# System.net
KiCad netlist of a schematic drawn in Altium Designer
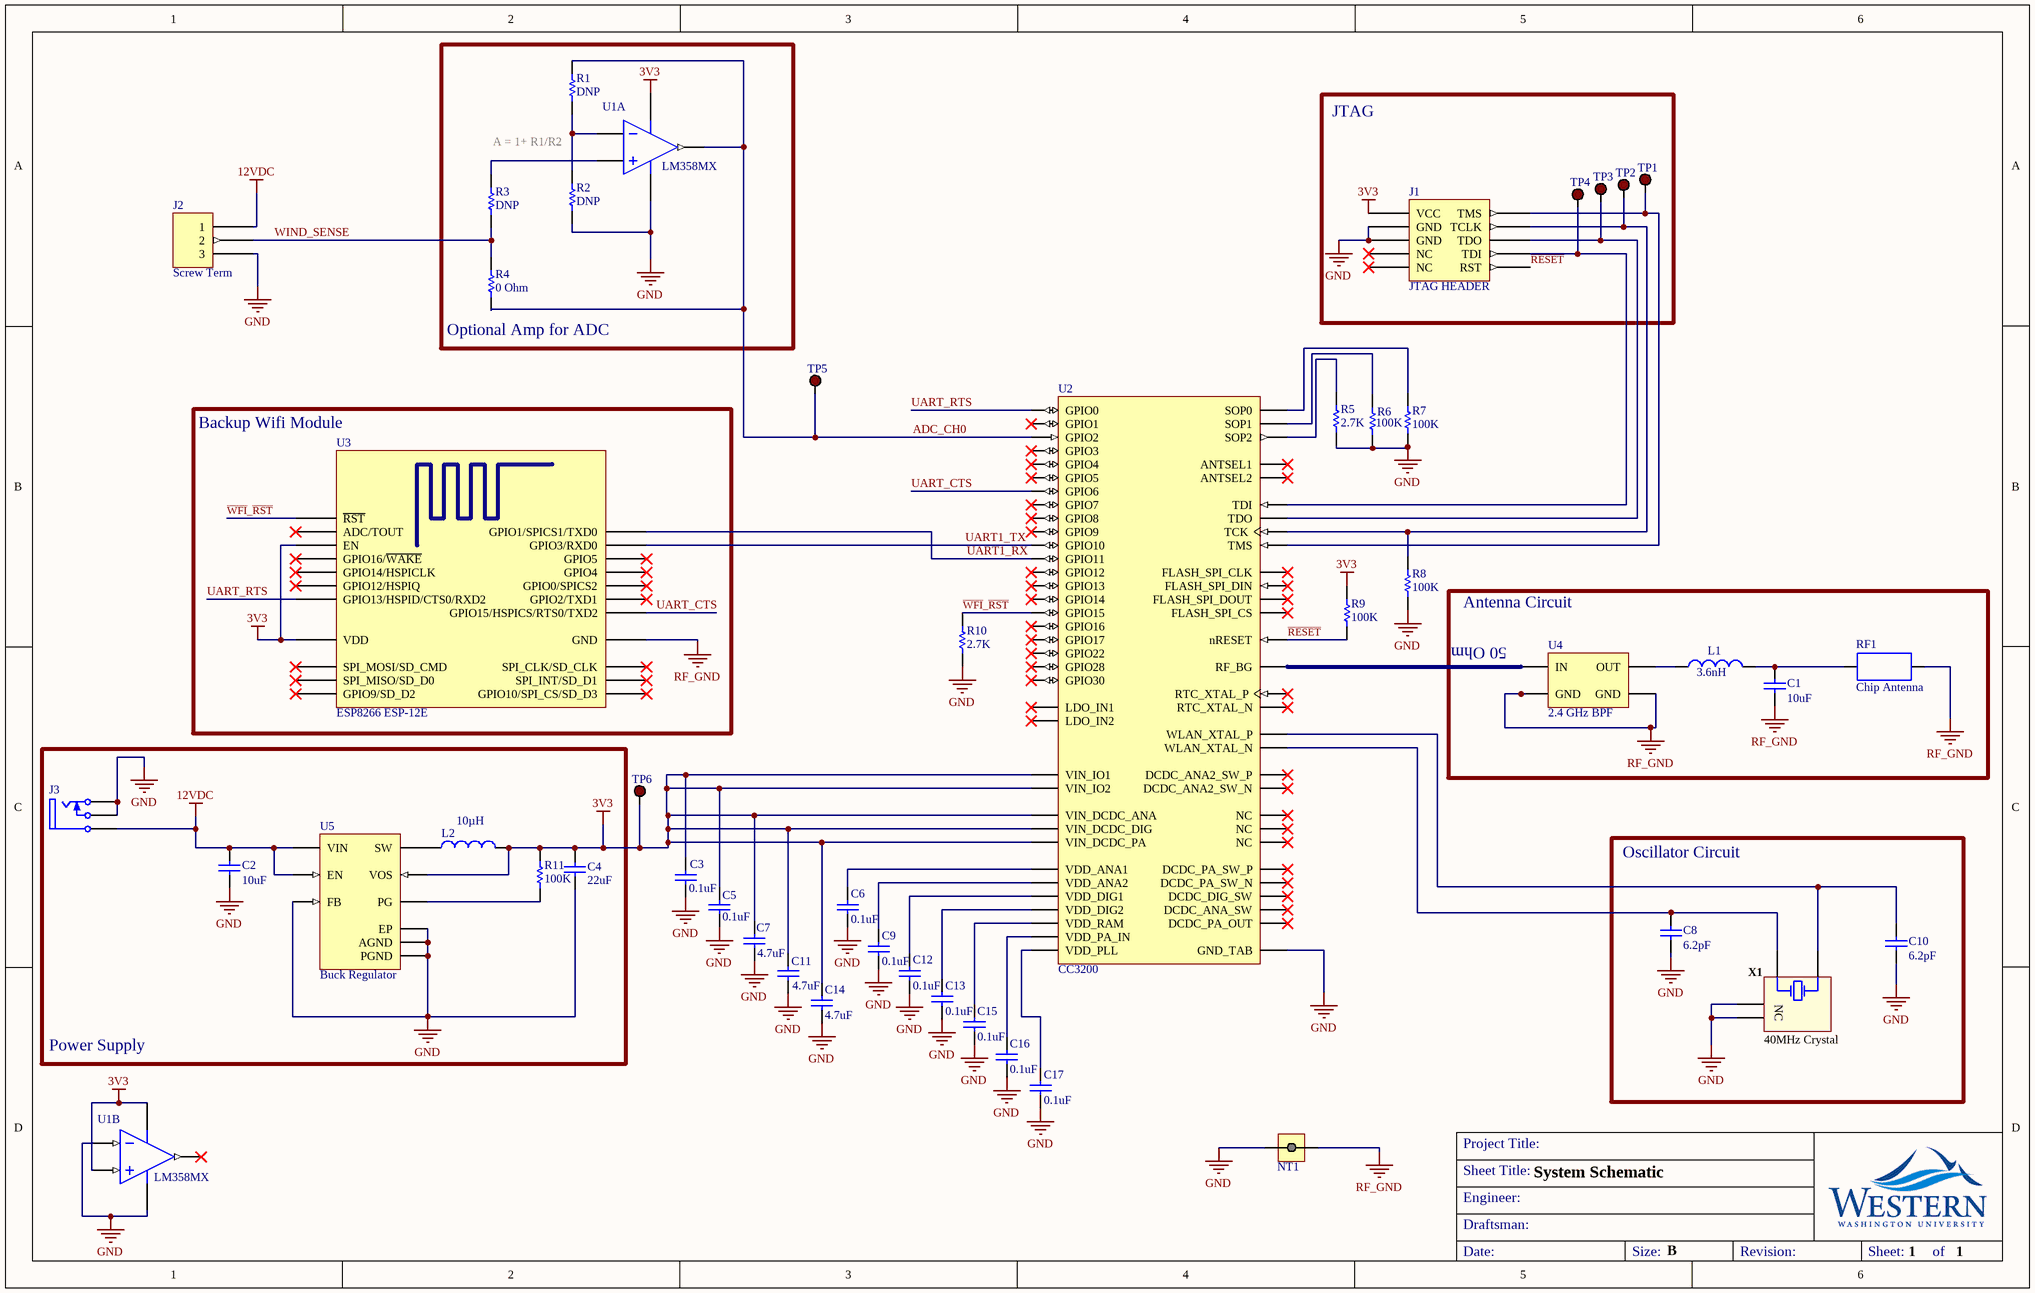
[diagram p0: System.SchDoc]

(export (version "E")
  (design (tool "Eeschema 10.0.6"))
  (components
    (comp (ref "C1")
      (value "10uF")
      (footprint "CAPC0603(1608)100_M")
      (description "CAP 10uF 10V ±20% 0603 (1608 Metric) Thickness 1mm SMD")
      (fields (field (name "TOLERANCE") "Â±20%") (field (name "Comment") "CAP 10uF 10V 0603(1608)"))
      (libsource (lib "Altium Content Vault") (part "CMP-1035-02800-1"))
    )
    (comp (ref "C2")
      (value "10uF")
      (footprint "CAPC0603(1608)100_M")
      (description "CAP 10uF 10V ±20% 0603 (1608 Metric) Thickness 1mm SMD")
      (fields (field (name "TOLERANCE") "Â±20%") (field (name "Comment") "CAP 10uF 10V 0603(1608)"))
      (libsource (lib "Altium Content Vault") (part "CMP-1035-02800-1"))
    )
    (comp (ref "C3")
      (value "0.1uF")
      (footprint "CAPC0603(1608)100_M")
      (description "CAP 10uF 10V ±20% 0603 (1608 Metric) Thickness 1mm SMD")
      (fields (field (name "TOLERANCE") "Â±20%") (field (name "Comment") "CAP 10uF 10V 0603(1608)"))
      (libsource (lib "Altium Content Vault") (part "CMP-1035-02800-1"))
    )
    (comp (ref "C4")
      (value "22uF")
      (footprint "CAPC0603(1608)100_L")
      (description "0603 (1608 Metric) Chip Capacitor")
      (libsource (lib "Altium Content Vault") (part "CAP_5"))
    )
    (comp (ref "C5")
      (value "0.1uF")
      (footprint "CAPC0603(1608)100_M")
      (description "CAP 10uF 10V ±20% 0603 (1608 Metric) Thickness 1mm SMD")
      (fields (field (name "TOLERANCE") "Â±20%") (field (name "Comment") "CAP 10uF 10V 0603(1608)"))
      (libsource (lib "Altium Content Vault") (part "CMP-1035-02800-1"))
    )
    (comp (ref "C6")
      (value "0.1uF")
      (footprint "CAPC0603(1608)100_M")
      (description "CAP 10uF 10V ±20% 0603 (1608 Metric) Thickness 1mm SMD")
      (fields (field (name "TOLERANCE") "Â±20%") (field (name "Comment") "CAP 10uF 10V 0603(1608)"))
      (libsource (lib "Altium Content Vault") (part "CMP-1035-02800-1"))
    )
    (comp (ref "C7")
      (value "4.7uF")
      (footprint "CAPC0603(1608)100_M")
      (description "CAP 10uF 10V ±20% 0603 (1608 Metric) Thickness 1mm SMD")
      (fields (field (name "TOLERANCE") "Â±20%") (field (name "Comment") "CAP 10uF 10V 0603(1608)"))
      (libsource (lib "Altium Content Vault") (part "CMP-1035-02800-1"))
    )
    (comp (ref "C8")
      (value "6.2pF")
      (footprint "CAPC0603(1608)100_M")
      (description "CAP 10uF 10V ±20% 0603 (1608 Metric) Thickness 1mm SMD")
      (fields (field (name "TOLERANCE") "Â±20%") (field (name "Comment") "CAP 10uF 10V 0603(1608)"))
      (libsource (lib "Altium Content Vault") (part "CMP-1035-02800-1"))
    )
    (comp (ref "C9")
      (value "0.1uF")
      (footprint "CAPC0603(1608)100_M")
      (description "CAP 10uF 10V ±20% 0603 (1608 Metric) Thickness 1mm SMD")
      (fields (field (name "TOLERANCE") "Â±20%") (field (name "Comment") "CAP 10uF 10V 0603(1608)"))
      (libsource (lib "Altium Content Vault") (part "CMP-1035-02800-1"))
    )
    (comp (ref "C10")
      (value "6.2pF")
      (footprint "CAPC0603(1608)100_M")
      (description "CAP 10uF 10V ±20% 0603 (1608 Metric) Thickness 1mm SMD")
      (fields (field (name "TOLERANCE") "Â±20%") (field (name "Comment") "CAP 10uF 10V 0603(1608)"))
      (libsource (lib "Altium Content Vault") (part "CMP-1035-02800-1"))
    )
    (comp (ref "C11")
      (value "4.7uF")
      (footprint "CAPC0603(1608)100_M")
      (description "CAP 10uF 10V ±20% 0603 (1608 Metric) Thickness 1mm SMD")
      (fields (field (name "TOLERANCE") "Â±20%") (field (name "Comment") "CAP 10uF 10V 0603(1608)"))
      (libsource (lib "Altium Content Vault") (part "CMP-1035-02800-1"))
    )
    (comp (ref "C12")
      (value "0.1uF")
      (footprint "CAPC0603(1608)100_M")
      (description "CAP 10uF 10V ±20% 0603 (1608 Metric) Thickness 1mm SMD")
      (fields (field (name "TOLERANCE") "Â±20%") (field (name "Comment") "CAP 10uF 10V 0603(1608)"))
      (libsource (lib "Altium Content Vault") (part "CMP-1035-02800-1"))
    )
    (comp (ref "C13")
      (value "0.1uF")
      (footprint "CAPC0603(1608)100_M")
      (description "CAP 10uF 10V ±20% 0603 (1608 Metric) Thickness 1mm SMD")
      (fields (field (name "TOLERANCE") "Â±20%") (field (name "Comment") "CAP 10uF 10V 0603(1608)"))
      (libsource (lib "Altium Content Vault") (part "CMP-1035-02800-1"))
    )
    (comp (ref "C14")
      (value "4.7uF")
      (footprint "CAPC0603(1608)100_M")
      (description "CAP 10uF 10V ±20% 0603 (1608 Metric) Thickness 1mm SMD")
      (fields (field (name "TOLERANCE") "Â±20%") (field (name "Comment") "CAP 10uF 10V 0603(1608)"))
      (libsource (lib "Altium Content Vault") (part "CMP-1035-02800-1"))
    )
    (comp (ref "C15")
      (value "0.1uF")
      (footprint "CAPC0603(1608)100_M")
      (description "CAP 10uF 10V ±20% 0603 (1608 Metric) Thickness 1mm SMD")
      (fields (field (name "TOLERANCE") "Â±20%") (field (name "Comment") "CAP 10uF 10V 0603(1608)"))
      (libsource (lib "Altium Content Vault") (part "CMP-1035-02800-1"))
    )
    (comp (ref "C16")
      (value "0.1uF")
      (footprint "CAPC0603(1608)100_M")
      (description "CAP 10uF 10V ±20% 0603 (1608 Metric) Thickness 1mm SMD")
      (fields (field (name "TOLERANCE") "Â±20%") (field (name "Comment") "CAP 10uF 10V 0603(1608)"))
      (libsource (lib "Altium Content Vault") (part "CMP-1035-02800-1"))
    )
    (comp (ref "C17")
      (value "0.1uF")
      (footprint "CAPC0603(1608)100_M")
      (description "CAP 10uF 10V ±20% 0603 (1608 Metric) Thickness 1mm SMD")
      (fields (field (name "TOLERANCE") "Â±20%") (field (name "Comment") "CAP 10uF 10V 0603(1608)"))
      (libsource (lib "Altium Content Vault") (part "CMP-1035-02800-1"))
    )
    (comp (ref "J1")
      (value "JTAG HEADER")
      (footprint "FTSH-105-01-L-DV-K")
      (description "10 pin 0.05\" pitch header for JTAG")
      (libsource (lib "WWUEE_SchematicLibrary") (part "JTAG 10 PIN HEADER"))
    )
    (comp (ref "J2")
      (value "Screw Term")
      (footprint "SCREW TERM 3 PIN 3.5mm")
      (libsource (lib "WWUEE_SchematicLibrary") (part "SCREW TERM 3.5mm 3pos"))
    )
    (comp (ref "J3")
      (value "RASM722X")
      (footprint "SWIT-RASM722X_V")
      (description "Power Jack, 5 A, 250 V, 3-Pin SMD, RoHS, Bulk")
      (libsource (lib "Altium Content Vault") (part "CMP-1772-00002-1"))
    )
    (comp (ref "L1")
      (value "MLZ2012N100LT")
      (footprint "TDK-IND0805-125_V")
      (description "Multilayer Inductor, 10 uH, ±20%, 300 mOhm, 50MHz, 0805(2012)")
      (fields
        (field (name "MANUFACTURER") "TDK Corporation")
        (field (name "MANUFACTURER PART NUMBER") "MLZ2012N100LTD25")
        (field (name "INDUCTANCE") "3.6nH")
      )
      (libsource (lib "Altium Content Vault") (part "CMP-0266-00001-1"))
    )
    (comp (ref "L2")
      (value "MLZ2012N100LT")
      (footprint "TDK-IND0805-125_V")
      (description "Multilayer Inductor, 10 uH, ±20%, 300 mOhm, 50MHz, 0805(2012)")
      (fields
        (field (name "MANUFACTURER") "TDK Corporation")
        (field (name "MANUFACTURER PART NUMBER") "MLZ2012N100LTD25")
        (field (name "INDUCTANCE") "10µH")
      )
      (libsource (lib "Altium Content Vault") (part "CMP-0266-00001-1"))
    )
    (comp (ref "NT1")
      (value "NET TIE 0603")
      (footprint "NetTie0603")
      (libsource (lib "WWUEE_SchematicLibrary") (part "NET TIE"))
    )
    (comp (ref "R1")
      (value "DNP")
      (footprint "RESC0603(1608)_N")
      (description "Jumper 0603 (1608 Metric)")
      (fields (field (name "POWER") "None"))
      (libsource (lib "Altium Content Vault") (part "CMP-1012-00001-1"))
    )
    (comp (ref "R2")
      (value "DNP")
      (footprint "RESC0603(1608)_N")
      (description "Jumper 0603 (1608 Metric)")
      (fields (field (name "POWER") "None"))
      (libsource (lib "Altium Content Vault") (part "CMP-1012-00001-1"))
    )
    (comp (ref "R3")
      (value "DNP")
      (footprint "RESC0603(1608)_N")
      (description "Jumper 0603 (1608 Metric)")
      (fields (field (name "POWER") "None"))
      (libsource (lib "Altium Content Vault") (part "CMP-1012-00001-1"))
    )
    (comp (ref "R4")
      (value "0 Ohm")
      (footprint "RESC0603(1608)_N")
      (description "Jumper 0603 (1608 Metric)")
      (fields (field (name "POWER") "None"))
      (libsource (lib "Altium Content Vault") (part "RES"))
    )
    (comp (ref "R5")
      (value "2.7K")
      (footprint "RESC0805(2012)_L")
      (description "100K 0.125W 5% 0805 (2012 Metric)  SMD")
      (fields (field (name "TOLERANCE") "5 %") (field (name "POWER") "0.125 W"))
      (libsource (lib "Altium Content Vault") (part "RES"))
    )
    (comp (ref "R6")
      (value "100K")
      (footprint "RESC0805(2012)_L")
      (description "100K 0.125W 5% 0805 (2012 Metric)  SMD")
      (fields (field (name "TOLERANCE") "5 %") (field (name "POWER") "0.125 W"))
      (libsource (lib "Altium Content Vault") (part "RES"))
    )
    (comp (ref "R7")
      (value "100K")
      (footprint "RESC0805(2012)_L")
      (description "100K 0.125W 5% 0805 (2012 Metric)  SMD")
      (fields (field (name "TOLERANCE") "5 %") (field (name "POWER") "0.125 W"))
      (libsource (lib "Altium Content Vault") (part "RES"))
    )
    (comp (ref "R8")
      (value "100K")
      (footprint "RESC0805(2012)_L")
      (description "100K 0.125W 5% 0805 (2012 Metric)  SMD")
      (fields (field (name "TOLERANCE") "5 %") (field (name "POWER") "0.125 W"))
      (libsource (lib "Altium Content Vault") (part "RES"))
    )
    (comp (ref "R9")
      (value "100K")
      (footprint "RESC0805(2012)_L")
      (description "100K 0.125W 5% 0805 (2012 Metric)  SMD")
      (fields (field (name "TOLERANCE") "5 %") (field (name "POWER") "0.125 W"))
      (libsource (lib "Altium Content Vault") (part "RES"))
    )
    (comp (ref "R10")
      (value "2.7K")
      (footprint "RESC0805(2012)_L")
      (description "100K 0.125W 5% 0805 (2012 Metric)  SMD")
      (fields (field (name "TOLERANCE") "5 %") (field (name "POWER") "0.125 W"))
      (libsource (lib "Altium Content Vault") (part "RES"))
    )
    (comp (ref "R11")
      (value "100K")
      (footprint "RESC0805(2012)_L")
      (description "100K 0.125W 5% 0805 (2012 Metric)  SMD")
      (fields (field (name "TOLERANCE") "5 %") (field (name "POWER") "0.125 W"))
      (libsource (lib "Altium Content Vault") (part "RES"))
    )
    (comp (ref "RF1")
      (value "Chip Antenna")
      (footprint "TAYO-AH316M-2_N")
      (description "Chip Antenna, 2.4 to 2.5 GHz, -40 to 85 degC, 2-Pin SMD, Pb-Free, Tape and Reel")
      (fields (field (name "TOLERANCE") "10%"))
      (libsource (lib "Altium Content Vault") (part "CMP-1660-00004-1"))
    )
    (comp (ref "TP1")
      (value "5001")
      (footprint "Keystone_5001")
      (description "TEST POINT PC MINI .040\"D BLACK")
      (fields (field (name "MANUFACTURER") "Keystone Electronics"))
      (libsource (lib "WWUEE_SchematicLibrary") (part "TEST POINT"))
    )
    (comp (ref "TP2")
      (value "5001")
      (footprint "Keystone_5001")
      (description "TEST POINT PC MINI .040\"D BLACK")
      (fields (field (name "MANUFACTURER") "Keystone Electronics"))
      (libsource (lib "WWUEE_SchematicLibrary") (part "TEST POINT"))
    )
    (comp (ref "TP3")
      (value "5001")
      (footprint "Keystone_5001")
      (description "TEST POINT PC MINI .040\"D BLACK")
      (fields (field (name "MANUFACTURER") "Keystone Electronics"))
      (libsource (lib "WWUEE_SchematicLibrary") (part "TEST POINT"))
    )
    (comp (ref "TP4")
      (value "5001")
      (footprint "Keystone_5001")
      (description "TEST POINT PC MINI .040\"D BLACK")
      (fields (field (name "MANUFACTURER") "Keystone Electronics"))
      (libsource (lib "WWUEE_SchematicLibrary") (part "TEST POINT"))
    )
    (comp (ref "TP5")
      (value "5001")
      (footprint "Keystone_5001")
      (description "TEST POINT PC MINI .040\"D BLACK")
      (fields (field (name "MANUFACTURER") "Keystone Electronics"))
      (libsource (lib "WWUEE_SchematicLibrary") (part "TEST POINT"))
    )
    (comp (ref "TP6")
      (value "5001")
      (footprint "Keystone_5001")
      (description "TEST POINT PC MINI .040\"D BLACK")
      (fields (field (name "MANUFACTURER") "Keystone Electronics"))
      (libsource (lib "WWUEE_SchematicLibrary") (part "TEST POINT"))
    )
    (comp (ref "U1")
      (value "LM358MX")
      (footprint "M08A_L")
      (description "Low Power Dual Operational Amplifier, 8-pin Narrow SOIC")
      (fields (field (name "MANUFACTURER") "National Semiconductor"))
      (libsource (lib "Altium Content Vault") (part "CMP-0055-00630-1"))
    )
    (comp (ref "U2")
      (value "CC3200")
      (footprint "TI-RGC64-7300x7300TP_L")
      (fields (field (name "PARTNUMBER") "CC3200R1M2RGC") (field (name "MANUFACTURER") "Texas Instruments"))
      (libsource (lib "altium-import") (part "root_0_CMP-1530-00002-1_"))
    )
    (comp (ref "U3")
      (value "ESP8266 ESP-12E")
      (footprint "ESP8266:ESP8266 ESP-12-E")
      (description "ESP8266 ESP-12-E")
      (libsource (lib "ESP8266") (part "ESP8266 ESP-12-E"))
    )
    (comp (ref "U4")
      (value "2.4 GHz BPF")
      (footprint "TDK-DEA202450BT-1294C1-H_V")
      (description "2.4 GHz Filter")
      (fields (field (name "TOLERANCE") "1%"))
      (libsource (lib "Altium Content Vault") (part "CMP-1663-00013-1"))
    )
    (comp (ref "U5")
      (value "Buck Regulator")
      (footprint "DSG0008A_V")
      (fields (field (name "MANUFACTURER") "Texas Instruments") (field (name "PARTNUMBER") "TPS62172DSGR"))
      (libsource (lib "Altium Content Vault") (part "CMP-0323-00337-3"))
    )
    (comp (ref "X1")
      (value "40MHz Crystal")
      (footprint "AVX-CX3225GB-4_V")
      (description "Crystal Unit, 8 pF, 25000 kHz, -10 to 70 degC, 4-Pin 3.2 x 2.5 x 0.8 mm SMD, RoHS, Tape and Reel")
      (fields (field (name "MANUFACTURER") "Kyocera") (field (name "PARTNUMBER") "CX3225GB25000D0HEQCC"))
      (libsource (lib "Altium Content Vault") (part "CMP-0614-00001-1"))
    )
  )
  (nets
    (net (code "1") (name "/ADC_CH0") (class "Default")
      (node (ref "R1") (pin "2") (pinfunction "2_2") (pintype "passive"))
      (node (ref "R4") (pin "1") (pinfunction "1_1") (pintype "passive"))
      (node (ref "TP5") (pin "1") (pinfunction "TP_1") (pintype "passive"))
      (node (ref "U1") (pin "1") (pinfunction "OUTA_1") (pintype "output"))
      (node (ref "U2") (pin "57") (pinfunction "GPIO2_57") (pintype "input"))
    )
    (net (code "2") (name "/UART1_RX") (class "Default")
      (node (ref "U2") (pin "2") (pinfunction "GPIO11_2") (pintype "bidirectional"))
      (node (ref "U3") (pin "22") (pinfunction "GPIO1/SPICS1/TXD0_22") (pintype "passive"))
    )
    (net (code "3") (name "/UART1_TX") (class "Default")
      (node (ref "U2") (pin "1") (pinfunction "GPIO10_1") (pintype "bidirectional"))
      (node (ref "U3") (pin "21") (pinfunction "GPIO3/RXD0_21") (pintype "passive"))
    )
    (net (code "4") (name "/UART_CTS") (class "Default")
      (node (ref "U2") (pin "61") (pinfunction "GPIO6_61") (pintype "bidirectional"))
      (node (ref "U3") (pin "16") (pinfunction "GPIO15/HSPICS/RTS0/TXD2_16") (pintype "passive"))
    )
    (net (code "5") (name "/UART_RTS") (class "Default")
      (node (ref "U2") (pin "50") (pinfunction "GPIO0_50") (pintype "bidirectional"))
      (node (ref "U3") (pin "7") (pinfunction "GPIO13/HSPID/CTS0/RXD2_7") (pintype "passive"))
    )
    (net (code "6") (name "/WIND_SENSE") (class "Default")
      (node (ref "J2") (pin "2") (pinfunction "2_2") (pintype "output"))
      (node (ref "R3") (pin "1") (pinfunction "1_1") (pintype "passive"))
      (node (ref "R4") (pin "2") (pinfunction "2_2") (pintype "passive"))
    )
    (net (code "7") (name "/~{RESET}") (class "Default")
      (node (ref "J1") (pin "10") (pinfunction "RST_10") (pintype "output"))
      (node (ref "R9") (pin "1") (pinfunction "1_1") (pintype "passive"))
      (node (ref "U2") (pin "32") (pinfunction "nRESET_32") (pintype "input"))
    )
    (net (code "8") (name "/~{WFI}_~{RST}") (class "Default")
      (node (ref "R10") (pin "2") (pinfunction "2_2") (pintype "passive"))
      (node (ref "U2") (pin "6") (pinfunction "GPIO15_6") (pintype "bidirectional"))
      (node (ref "U3") (pin "1") (pinfunction "~{RST}_1") (pintype "passive"))
    )
    (net (code "9") (name "3V3") (class "Default")
      (node (ref "C11") (pin "2") (pinfunction "2_2") (pintype "passive"))
      (node (ref "C14") (pin "2") (pinfunction "2_2") (pintype "passive"))
      (node (ref "C3") (pin "1") (pinfunction "1_1") (pintype "passive"))
      (node (ref "C4") (pin "2") (pinfunction "2_2") (pintype "passive"))
      (node (ref "C5") (pin "1") (pinfunction "1_1") (pintype "passive"))
      (node (ref "C7") (pin "2") (pinfunction "2_2") (pintype "passive"))
      (node (ref "J1") (pin "1") (pinfunction "VCC_1") (pintype "passive"))
      (node (ref "L2") (pin "2") (pinfunction "2_2") (pintype "passive"))
      (node (ref "R11") (pin "2") (pinfunction "2_2") (pintype "passive"))
      (node (ref "R9") (pin "2") (pinfunction "2_2") (pintype "passive"))
      (node (ref "TP6") (pin "1") (pinfunction "TP_1") (pintype "passive"))
      (node (ref "U1") (pin "5") (pinfunction "INB+_5") (pintype "input"))
      (node (ref "U1") (pin "8") (pinfunction "V+_8") (pintype "power_in"))
      (node (ref "U2") (pin "10") (pinfunction "VIN_IO1_10") (pintype "power_in"))
      (node (ref "U2") (pin "37") (pinfunction "VIN_DCDC_ANA_37") (pintype "power_in"))
      (node (ref "U2") (pin "39") (pinfunction "VIN_DCDC_PA_39") (pintype "power_in"))
      (node (ref "U2") (pin "44") (pinfunction "VIN_DCDC_DIG_44") (pintype "power_in"))
      (node (ref "U2") (pin "54") (pinfunction "VIN_IO2_54") (pintype "power_in"))
      (node (ref "U3") (pin "3") (pinfunction "EN_3") (pintype "passive"))
      (node (ref "U3") (pin "8") (pinfunction "VDD_8") (pintype "passive"))
      (node (ref "U5") (pin "6") (pinfunction "VOS_6") (pintype "input"))
    )
    (net (code "10") (name "12VDC") (class "Default")
      (node (ref "C2") (pin "2") (pinfunction "2_2") (pintype "passive"))
      (node (ref "J2") (pin "1") (pinfunction "1_1") (pintype "passive"))
      (node (ref "J3") (pin "1") (pinfunction "SLEEVE_1") (pintype "passive"))
      (node (ref "U5") (pin "2") (pinfunction "VIN_2") (pintype "power_in"))
      (node (ref "U5") (pin "3") (pinfunction "EN_3") (pintype "input"))
    )
    (net (code "11") (name "GND") (class "Default")
      (node (ref "C10") (pin "1") (pinfunction "1_1") (pintype "passive"))
      (node (ref "C11") (pin "1") (pinfunction "1_1") (pintype "passive"))
      (node (ref "C12") (pin "1") (pinfunction "1_1") (pintype "passive"))
      (node (ref "C13") (pin "1") (pinfunction "1_1") (pintype "passive"))
      (node (ref "C14") (pin "1") (pinfunction "1_1") (pintype "passive"))
      (node (ref "C15") (pin "1") (pinfunction "1_1") (pintype "passive"))
      (node (ref "C16") (pin "1") (pinfunction "1_1") (pintype "passive"))
      (node (ref "C17") (pin "1") (pinfunction "1_1") (pintype "passive"))
      (node (ref "C2") (pin "1") (pinfunction "1_1") (pintype "passive"))
      (node (ref "C3") (pin "2") (pinfunction "2_2") (pintype "passive"))
      (node (ref "C4") (pin "1") (pinfunction "1_1") (pintype "passive"))
      (node (ref "C5") (pin "2") (pinfunction "2_2") (pintype "passive"))
      (node (ref "C6") (pin "1") (pinfunction "1_1") (pintype "passive"))
      (node (ref "C7") (pin "1") (pinfunction "1_1") (pintype "passive"))
      (node (ref "C8") (pin "1") (pinfunction "1_1") (pintype "passive"))
      (node (ref "C9") (pin "1") (pinfunction "1_1") (pintype "passive"))
      (node (ref "J1") (pin "3") (pinfunction "GND_3") (pintype "passive"))
      (node (ref "J1") (pin "5") (pinfunction "GND_5") (pintype "passive"))
      (node (ref "J2") (pin "3") (pinfunction "3_3") (pintype "passive"))
      (node (ref "J3") (pin "2") (pinfunction "TIP_2") (pintype "passive"))
      (node (ref "J3") (pin "3") (pinfunction "SHUNT_3") (pintype "passive"))
      (node (ref "NT1") (pin "1") (pinfunction "1_1") (pintype "passive"))
      (node (ref "R10") (pin "1") (pinfunction "1_1") (pintype "passive"))
      (node (ref "R2") (pin "1") (pinfunction "1_1") (pintype "passive"))
      (node (ref "R5") (pin "1") (pinfunction "1_1") (pintype "passive"))
      (node (ref "R6") (pin "1") (pinfunction "1_1") (pintype "passive"))
      (node (ref "R7") (pin "1") (pinfunction "1_1") (pintype "passive"))
      (node (ref "R8") (pin "1") (pinfunction "1_1") (pintype "passive"))
      (node (ref "U1") (pin "4") (pinfunction "GND_4") (pintype "power_in"))
      (node (ref "U1") (pin "6") (pinfunction "INB-_6") (pintype "input"))
      (node (ref "U2") (pin "65") (pinfunction "GND_TAB_65") (pintype "power_in"))
      (node (ref "U5") (pin "1") (pinfunction "PGND_1") (pintype "power_in"))
      (node (ref "U5") (pin "4") (pinfunction "AGND_4") (pintype "power_in"))
      (node (ref "U5") (pin "5") (pinfunction "FB_5") (pintype "input"))
      (node (ref "U5") (pin "9") (pinfunction "EP_9") (pintype "power_in"))
      (node (ref "X1") (pin "2") (pinfunction "NC_2") (pintype "passive"))
      (node (ref "X1") (pin "4") (pinfunction "NC_4") (pintype "passive"))
    )
    (net (code "12") (name "Net-(C1-Pad2)") (class "Default")
      (node (ref "C1") (pin "2") (pinfunction "2_2") (pintype "passive"))
      (node (ref "L1") (pin "2") (pinfunction "2_2") (pintype "passive"))
      (node (ref "RF1") (pin "1") (pinfunction "1_1") (pintype "passive"))
    )
    (net (code "13") (name "Net-(J1-TCLK)") (class "Default")
      (node (ref "J1") (pin "4") (pinfunction "TCLK_4") (pintype "output"))
      (node (ref "R8") (pin "2") (pinfunction "2_2") (pintype "passive"))
      (node (ref "TP2") (pin "1") (pinfunction "TP_1") (pintype "passive"))
      (node (ref "U2") (pin "19") (pinfunction "TCK_19") (pintype "input"))
    )
    (net (code "14") (name "Net-(J1-TDI)") (class "Default")
      (node (ref "J1") (pin "8") (pinfunction "TDI_8") (pintype "output"))
      (node (ref "TP4") (pin "1") (pinfunction "TP_1") (pintype "passive"))
      (node (ref "U2") (pin "16") (pinfunction "TDI_16") (pintype "input"))
    )
    (net (code "15") (name "Net-(J1-TDO)") (class "Default")
      (node (ref "J1") (pin "6") (pinfunction "TDO_6") (pintype "passive"))
      (node (ref "TP3") (pin "1") (pinfunction "TP_1") (pintype "passive"))
      (node (ref "U2") (pin "17") (pinfunction "TDO_17") (pintype "tri_state"))
    )
    (net (code "16") (name "Net-(J1-TMS)") (class "Default")
      (node (ref "J1") (pin "2") (pinfunction "TMS_2") (pintype "output"))
      (node (ref "TP1") (pin "1") (pinfunction "TP_1") (pintype "passive"))
      (node (ref "U2") (pin "20") (pinfunction "TMS_20") (pintype "input"))
    )
    (net (code "17") (name "Net-(U1A-INA+)") (class "Default")
      (node (ref "R3") (pin "2") (pinfunction "2_2") (pintype "passive"))
      (node (ref "U1") (pin "3") (pinfunction "INA+_3") (pintype "passive"))
    )
    (net (code "18") (name "Net-(U1A-INA-)") (class "Default")
      (node (ref "R1") (pin "1") (pinfunction "1_1") (pintype "passive"))
      (node (ref "R2") (pin "2") (pinfunction "2_2") (pintype "passive"))
      (node (ref "U1") (pin "2") (pinfunction "INA-_2") (pintype "passive"))
    )
    (net (code "19") (name "Net-(U2-RF_BG)") (class "Default")
      (node (ref "U2") (pin "31") (pinfunction "RF_BG_31") (pintype "passive"))
      (node (ref "U4") (pin "1") (pinfunction "IN_1") (pintype "power_in"))
    )
    (net (code "20") (name "Net-(U2-SOP0)") (class "Default")
      (node (ref "R7") (pin "2") (pinfunction "2_2") (pintype "passive"))
      (node (ref "U2") (pin "35") (pinfunction "SOP0_35") (pintype "passive"))
    )
    (net (code "21") (name "Net-(U2-SOP1)") (class "Default")
      (node (ref "R6") (pin "2") (pinfunction "2_2") (pintype "passive"))
      (node (ref "U2") (pin "34") (pinfunction "SOP1_34") (pintype "passive"))
    )
    (net (code "22") (name "Net-(U2-SOP2)") (class "Default")
      (node (ref "R5") (pin "2") (pinfunction "2_2") (pintype "passive"))
      (node (ref "U2") (pin "21") (pinfunction "SOP2_21") (pintype "output"))
    )
    (net (code "23") (name "Net-(U2-VDD_ANA1)") (class "Default")
      (node (ref "C6") (pin "2") (pinfunction "2_2") (pintype "passive"))
      (node (ref "U2") (pin "48") (pinfunction "VDD_ANA1_48") (pintype "power_in"))
    )
    (net (code "24") (name "Net-(U2-VDD_ANA2)") (class "Default")
      (node (ref "C9") (pin "2") (pinfunction "2_2") (pintype "passive"))
      (node (ref "U2") (pin "47") (pinfunction "VDD_ANA2_47") (pintype "power_in"))
    )
    (net (code "25") (name "Net-(U2-VDD_DIG1)") (class "Default")
      (node (ref "C12") (pin "2") (pinfunction "2_2") (pintype "passive"))
      (node (ref "U2") (pin "9") (pinfunction "VDD_DIG1_9") (pintype "power_in"))
    )
    (net (code "26") (name "Net-(U2-VDD_DIG2)") (class "Default")
      (node (ref "C13") (pin "2") (pinfunction "2_2") (pintype "passive"))
      (node (ref "U2") (pin "56") (pinfunction "VDD_DIG2_56") (pintype "power_in"))
    )
    (net (code "27") (name "Net-(U2-VDD_PA_IN)") (class "Default")
      (node (ref "C16") (pin "2") (pinfunction "2_2") (pintype "passive"))
      (node (ref "U2") (pin "33") (pinfunction "VDD_PA_IN_33") (pintype "power_in"))
    )
    (net (code "28") (name "Net-(U2-VDD_PLL)") (class "Default")
      (node (ref "C17") (pin "2") (pinfunction "2_2") (pintype "passive"))
      (node (ref "U2") (pin "24") (pinfunction "VDD_PLL_24") (pintype "power_in"))
    )
    (net (code "29") (name "Net-(U2-VDD_RAM)") (class "Default")
      (node (ref "C15") (pin "2") (pinfunction "2_2") (pintype "passive"))
      (node (ref "U2") (pin "49") (pinfunction "VDD_RAM_49") (pintype "power_in"))
    )
    (net (code "30") (name "Net-(U2-WLAN_XTAL_N)") (class "Default")
      (node (ref "C8") (pin "2") (pinfunction "2_2") (pintype "passive"))
      (node (ref "U2") (pin "22") (pinfunction "WLAN_XTAL_N_22") (pintype "passive"))
      (node (ref "X1") (pin "3") (pinfunction "HOT_3") (pintype "passive"))
    )
    (net (code "31") (name "Net-(U2-WLAN_XTAL_P)") (class "Default")
      (node (ref "C10") (pin "2") (pinfunction "2_2") (pintype "passive"))
      (node (ref "U2") (pin "23") (pinfunction "WLAN_XTAL_P_23") (pintype "passive"))
      (node (ref "X1") (pin "1") (pinfunction "HOT_1") (pintype "passive"))
    )
    (net (code "32") (name "Net-(U4-OUT)") (class "Default")
      (node (ref "L1") (pin "1") (pinfunction "1_1") (pintype "passive"))
      (node (ref "U4") (pin "3") (pinfunction "OUT_3") (pintype "power_in"))
    )
    (net (code "33") (name "Net-(U5-PG)") (class "Default")
      (node (ref "R11") (pin "1") (pinfunction "1_1") (pintype "passive"))
      (node (ref "U5") (pin "8") (pinfunction "PG_8") (pintype "tri_state"))
    )
    (net (code "34") (name "Net-(U5-SW)") (class "Default")
      (node (ref "L2") (pin "1") (pinfunction "1_1") (pintype "passive"))
      (node (ref "U5") (pin "7") (pinfunction "SW_7") (pintype "power_in"))
    )
    (net (code "35") (name "RF_GND") (class "Default")
      (node (ref "C1") (pin "1") (pinfunction "1_1") (pintype "passive"))
      (node (ref "NT1") (pin "2") (pinfunction "2_2") (pintype "passive"))
      (node (ref "RF1") (pin "2") (pinfunction "2_2") (pintype "passive"))
      (node (ref "U3") (pin "15") (pinfunction "GND_15") (pintype "passive"))
      (node (ref "U4") (pin "2") (pinfunction "GND_2") (pintype "power_in"))
      (node (ref "U4") (pin "4") (pinfunction "GND_4") (pintype "power_in"))
    )
    (net (code "36") (name "unconnected-(J1-NC-Pad7)") (class "Default")
      (node (ref "J1") (pin "7") (pinfunction "NC_7") (pintype "passive+no_connect"))
    )
    (net (code "37") (name "unconnected-(J1-NC-Pad9)") (class "Default")
      (node (ref "J1") (pin "9") (pinfunction "NC_9") (pintype "passive+no_connect"))
    )
    (net (code "38") (name "unconnected-(U1B-OUTB-Pad7)") (class "Default")
      (node (ref "U1") (pin "7") (pinfunction "OUTB_7") (pintype "output+no_connect"))
    )
    (net (code "39") (name "unconnected-(U2-ANTSEL1-Pad29)") (class "Default")
      (node (ref "U2") (pin "29") (pinfunction "ANTSEL1_29") (pintype "tri_state+no_connect"))
    )
    (net (code "40") (name "unconnected-(U2-ANTSEL2-Pad30)") (class "Default")
      (node (ref "U2") (pin "30") (pinfunction "ANTSEL2_30") (pintype "tri_state+no_connect"))
    )
    (net (code "41") (name "unconnected-(U2-DCDC_ANA2_SW_N-Pad46)") (class "Default")
      (node (ref "U2") (pin "46") (pinfunction "DCDC_ANA2_SW_N_46") (pintype "passive+no_connect"))
    )
    (net (code "42") (name "unconnected-(U2-DCDC_ANA2_SW_P-Pad45)") (class "Default")
      (node (ref "U2") (pin "45") (pinfunction "DCDC_ANA2_SW_P_45") (pintype "passive+no_connect"))
    )
    (net (code "43") (name "unconnected-(U2-DCDC_ANA_SW-Pad38)") (class "Default")
      (node (ref "U2") (pin "38") (pinfunction "DCDC_ANA_SW_38") (pintype "power_in+no_connect"))
    )
    (net (code "44") (name "unconnected-(U2-DCDC_DIG_SW-Pad43)") (class "Default")
      (node (ref "U2") (pin "43") (pinfunction "DCDC_DIG_SW_43") (pintype "power_in+no_connect"))
    )
    (net (code "45") (name "unconnected-(U2-DCDC_PA_OUT-Pad42)") (class "Default")
      (node (ref "U2") (pin "42") (pinfunction "DCDC_PA_OUT_42") (pintype "power_in+no_connect"))
    )
    (net (code "46") (name "unconnected-(U2-DCDC_PA_SW_N-Pad41)") (class "Default")
      (node (ref "U2") (pin "41") (pinfunction "DCDC_PA_SW_N_41") (pintype "power_in+no_connect"))
    )
    (net (code "47") (name "unconnected-(U2-DCDC_PA_SW_P-Pad40)") (class "Default")
      (node (ref "U2") (pin "40") (pinfunction "DCDC_PA_SW_P_40") (pintype "power_in+no_connect"))
    )
    (net (code "48") (name "unconnected-(U2-FLASH_SPI_CLK-Pad11)") (class "Default")
      (node (ref "U2") (pin "11") (pinfunction "FLASH_SPI_CLK_11") (pintype "tri_state+no_connect"))
    )
    (net (code "49") (name "unconnected-(U2-FLASH_SPI_CS-Pad14)") (class "Default")
      (node (ref "U2") (pin "14") (pinfunction "FLASH_SPI_CS_14") (pintype "tri_state+no_connect"))
    )
    (net (code "50") (name "unconnected-(U2-FLASH_SPI_DIN-Pad13)") (class "Default")
      (node (ref "U2") (pin "13") (pinfunction "FLASH_SPI_DIN_13") (pintype "input+no_connect"))
    )
    (net (code "51") (name "unconnected-(U2-FLASH_SPI_DOUT-Pad12)") (class "Default")
      (node (ref "U2") (pin "12") (pinfunction "FLASH_SPI_DOUT_12") (pintype "tri_state+no_connect"))
    )
    (net (code "52") (name "unconnected-(U2-GPIO1-Pad55)") (class "Default")
      (node (ref "U2") (pin "55") (pinfunction "GPIO1_55") (pintype "bidirectional+no_connect"))
    )
    (net (code "53") (name "unconnected-(U2-GPIO3-Pad58)") (class "Default")
      (node (ref "U2") (pin "58") (pinfunction "GPIO3_58") (pintype "bidirectional+no_connect"))
    )
    (net (code "54") (name "unconnected-(U2-GPIO4-Pad59)") (class "Default")
      (node (ref "U2") (pin "59") (pinfunction "GPIO4_59") (pintype "bidirectional+no_connect"))
    )
    (net (code "55") (name "unconnected-(U2-GPIO5-Pad60)") (class "Default")
      (node (ref "U2") (pin "60") (pinfunction "GPIO5_60") (pintype "bidirectional+no_connect"))
    )
    (net (code "56") (name "unconnected-(U2-GPIO7-Pad62)") (class "Default")
      (node (ref "U2") (pin "62") (pinfunction "GPIO7_62") (pintype "bidirectional+no_connect"))
    )
    (net (code "57") (name "unconnected-(U2-GPIO8-Pad63)") (class "Default")
      (node (ref "U2") (pin "63") (pinfunction "GPIO8_63") (pintype "bidirectional+no_connect"))
    )
    (net (code "58") (name "unconnected-(U2-GPIO9-Pad64)") (class "Default")
      (node (ref "U2") (pin "64") (pinfunction "GPIO9_64") (pintype "bidirectional+no_connect"))
    )
    (net (code "59") (name "unconnected-(U2-GPIO12-Pad3)") (class "Default")
      (node (ref "U2") (pin "3") (pinfunction "GPIO12_3") (pintype "bidirectional+no_connect"))
    )
    (net (code "60") (name "unconnected-(U2-GPIO13-Pad4)") (class "Default")
      (node (ref "U2") (pin "4") (pinfunction "GPIO13_4") (pintype "bidirectional+no_connect"))
    )
    (net (code "61") (name "unconnected-(U2-GPIO14-Pad5)") (class "Default")
      (node (ref "U2") (pin "5") (pinfunction "GPIO14_5") (pintype "bidirectional+no_connect"))
    )
    (net (code "62") (name "unconnected-(U2-GPIO16-Pad7)") (class "Default")
      (node (ref "U2") (pin "7") (pinfunction "GPIO16_7") (pintype "bidirectional+no_connect"))
    )
    (net (code "63") (name "unconnected-(U2-GPIO17-Pad8)") (class "Default")
      (node (ref "U2") (pin "8") (pinfunction "GPIO17_8") (pintype "bidirectional+no_connect"))
    )
    (net (code "64") (name "unconnected-(U2-GPIO22-Pad15)") (class "Default")
      (node (ref "U2") (pin "15") (pinfunction "GPIO22_15") (pintype "bidirectional+no_connect"))
    )
    (net (code "65") (name "unconnected-(U2-GPIO28-Pad18)") (class "Default")
      (node (ref "U2") (pin "18") (pinfunction "GPIO28_18") (pintype "bidirectional+no_connect"))
    )
    (net (code "66") (name "unconnected-(U2-GPIO30-Pad53)") (class "Default")
      (node (ref "U2") (pin "53") (pinfunction "GPIO30_53") (pintype "bidirectional+no_connect"))
    )
    (net (code "67") (name "unconnected-(U2-LDO_IN1-Pad36)") (class "Default")
      (node (ref "U2") (pin "36") (pinfunction "LDO_IN1_36") (pintype "power_in+no_connect"))
    )
    (net (code "68") (name "unconnected-(U2-LDO_IN2-Pad25)") (class "Default")
      (node (ref "U2") (pin "25") (pinfunction "LDO_IN2_25") (pintype "power_in+no_connect"))
    )
    (net (code "69") (name "unconnected-(U2-NC-Pad26)") (class "Default")
      (node (ref "U2") (pin "26") (pinfunction "NC_26") (pintype "passive+no_connect"))
    )
    (net (code "70") (name "unconnected-(U2-NC-Pad27)") (class "Default")
      (node (ref "U2") (pin "27") (pinfunction "NC_27") (pintype "passive+no_connect"))
    )
    (net (code "71") (name "unconnected-(U2-NC-Pad28)") (class "Default")
      (node (ref "U2") (pin "28") (pinfunction "NC_28") (pintype "passive+no_connect"))
    )
    (net (code "72") (name "unconnected-(U2-RTC_XTAL_N-Pad52)") (class "Default")
      (node (ref "U2") (pin "52") (pinfunction "RTC_XTAL_N_52") (pintype "passive+no_connect"))
    )
    (net (code "73") (name "unconnected-(U2-RTC_XTAL_P-Pad51)") (class "Default")
      (node (ref "U2") (pin "51") (pinfunction "RTC_XTAL_P_51") (pintype "input+no_connect"))
    )
    (net (code "74") (name "unconnected-(U3-ADC{slash}TOUT-Pad2)") (class "Default")
      (node (ref "U3") (pin "2") (pinfunction "ADC/TOUT_2") (pintype "passive+no_connect"))
    )
    (net (code "75") (name "unconnected-(U3-GPIO0{slash}SPICS2-Pad18)") (class "Default")
      (node (ref "U3") (pin "18") (pinfunction "GPIO0/SPICS2_18") (pintype "passive+no_connect"))
    )
    (net (code "76") (name "unconnected-(U3-GPIO2{slash}TXD1-Pad17)") (class "Default")
      (node (ref "U3") (pin "17") (pinfunction "GPIO2/TXD1_17") (pintype "passive+no_connect"))
    )
    (net (code "77") (name "unconnected-(U3-GPIO4-Pad19)") (class "Default")
      (node (ref "U3") (pin "19") (pinfunction "GPIO4_19") (pintype "passive+no_connect"))
    )
    (net (code "78") (name "unconnected-(U3-GPIO5-Pad20)") (class "Default")
      (node (ref "U3") (pin "20") (pinfunction "GPIO5_20") (pintype "passive+no_connect"))
    )
    (net (code "79") (name "unconnected-(U3-GPIO9{slash}SD_D2-Pad11)") (class "Default")
      (node (ref "U3") (pin "11") (pinfunction "GPIO9/SD_D2_11") (pintype "passive+no_connect"))
    )
    (net (code "80") (name "unconnected-(U3-GPIO10{slash}SPI_CS{slash}SD_D3-Pad12)") (class "Default")
      (node (ref "U3") (pin "12") (pinfunction "GPIO10/SPI_CS/SD_D3_12") (pintype "passive+no_connect"))
    )
    (net (code "81") (name "unconnected-(U3-GPIO12{slash}HSPIQ-Pad6)") (class "Default")
      (node (ref "U3") (pin "6") (pinfunction "GPIO12/HSPIQ_6") (pintype "passive+no_connect"))
    )
    (net (code "82") (name "unconnected-(U3-GPIO14{slash}HSPICLK-Pad5)") (class "Default")
      (node (ref "U3") (pin "5") (pinfunction "GPIO14/HSPICLK_5") (pintype "passive+no_connect"))
    )
    (net (code "83") (name "unconnected-(U3-GPIO16{slash}~{WAKE}-Pad4)") (class "Default")
      (node (ref "U3") (pin "4") (pinfunction "GPIO16/~{WAKE}_4") (pintype "passive+no_connect"))
    )
    (net (code "84") (name "unconnected-(U3-SPI_CLK{slash}SD_CLK-Pad14)") (class "Default")
      (node (ref "U3") (pin "14") (pinfunction "SPI_CLK/SD_CLK_14") (pintype "passive+no_connect"))
    )
    (net (code "85") (name "unconnected-(U3-SPI_INT{slash}SD_D1-Pad13)") (class "Default")
      (node (ref "U3") (pin "13") (pinfunction "SPI_INT/SD_D1_13") (pintype "passive+no_connect"))
    )
    (net (code "86") (name "unconnected-(U3-SPI_MISO{slash}SD_D0-Pad10)") (class "Default")
      (node (ref "U3") (pin "10") (pinfunction "SPI_MISO/SD_D0_10") (pintype "passive+no_connect"))
    )
    (net (code "87") (name "unconnected-(U3-SPI_MOSI{slash}SD_CMD-Pad9)") (class "Default")
      (node (ref "U3") (pin "9") (pinfunction "SPI_MOSI/SD_CMD_9") (pintype "passive+no_connect"))
    )
  )
)
